# MCU_STM32.net
KiCad netlist of a schematic drawn in Altium Designer
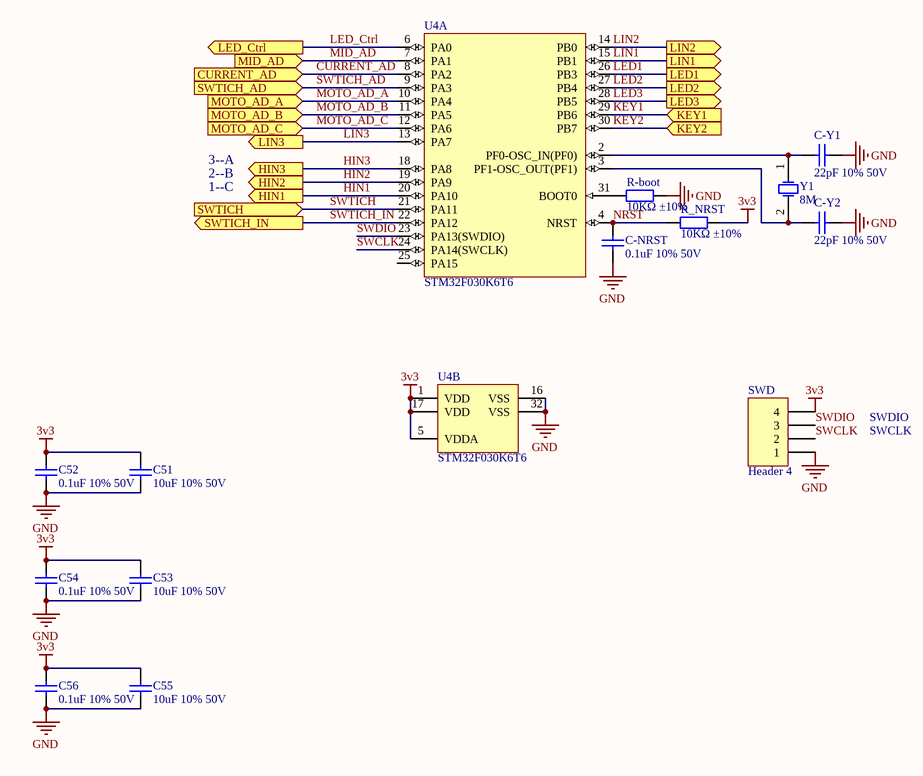
[diagram p0: MCU_STM32.SchDoc]

(export (version "E")
  (design (tool "Eeschema 10.0.6"))
  (components
    (comp (ref "C-NRST")
      (value "0.1uF 10% 50V")
      (footprint "0603_C")
      (description "贴片电容")
      (libsource (lib "Cap") (part "0603 4.7uF (475) 10% 16V"))
    )
    (comp (ref "C-Y1")
      (value "22pF 10% 50V")
      (footprint "0603_C")
      (description "贴片电容")
      (libsource (lib "Cap") (part "0603 4.7uF (475) 10% 16V"))
    )
    (comp (ref "C-Y2")
      (value "22pF 10% 50V")
      (footprint "0603_C")
      (description "贴片电容")
      (libsource (lib "Cap") (part "0603 4.7uF (475) 10% 16V"))
    )
    (comp (ref "C51")
      (value "10uF 10% 50V")
      (footprint "0805_C")
      (description "贴片电容")
      (libsource (lib "Cap") (part "0805 1uF (105) 10% 50V"))
    )
    (comp (ref "C52")
      (value "0.1uF 10% 50V")
      (footprint "0603_C")
      (description "贴片电容")
      (libsource (lib "Cap") (part "0603 4.7uF (475) 10% 16V"))
    )
    (comp (ref "C53")
      (value "10uF 10% 50V")
      (footprint "0805_C")
      (description "贴片电容")
      (libsource (lib "Cap") (part "0805 1uF (105) 10% 50V"))
    )
    (comp (ref "C54")
      (value "0.1uF 10% 50V")
      (footprint "0603_C")
      (description "贴片电容")
      (libsource (lib "Cap") (part "0603 4.7uF (475) 10% 16V"))
    )
    (comp (ref "C55")
      (value "10uF 10% 50V")
      (footprint "0805_C")
      (description "贴片电容")
      (libsource (lib "Cap") (part "0805 1uF (105) 10% 50V"))
    )
    (comp (ref "C56")
      (value "0.1uF 10% 50V")
      (footprint "0603_C")
      (description "贴片电容")
      (libsource (lib "Cap") (part "0603 4.7uF (475) 10% 16V"))
    )
    (comp (ref "R-boot")
      (value "10KΩ ±10%")
      (footprint "0603_R")
      (description "贴片电阻")
      (libsource (lib "RES") (part "0603 2.2Ω (2R20) 1%"))
    )
    (comp (ref "R_NRST")
      (value "10KΩ ±10%")
      (footprint "0603_R")
      (description "贴片电阻")
      (libsource (lib "RES") (part "0603 2.2Ω (2R20) 1%"))
    )
    (comp (ref "SWD")
      (value "Header 4")
      (footprint "FPC_1.25_4P")
      (description "Header, 4-Pin")
      (fields (field (name "PUBLISHER") "Altium Limited"))
      (libsource (lib "Miscellaneous Connectors") (part "Header 4"))
    )
    (comp (ref "U4")
      (value "STM32F030K6T6")
      (footprint "STM-LQFP32_M")
      (libsource (lib "MySTM32F0") (part "MC-ARM-STM32F030-SQ32"))
    )
    (comp (ref "Y1")
      (value "8M")
      (footprint "XTAL")
      (description "Crystal Oscillator")
      (fields (field (name "PUBLISHER") "Altium Limited"))
      (libsource (lib "Miscellaneous Devices") (part "XTAL"))
    )
  )
  (nets
    (net (code "1") (name "/CURRENT_AD") (class "Default")
      (node (ref "U4") (pin "8") (pinfunction "PA2_8") (pintype "bidirectional"))
    )
    (net (code "2") (name "/HIN1") (class "Default")
      (node (ref "U4") (pin "20") (pinfunction "PA10_20") (pintype "bidirectional"))
    )
    (net (code "3") (name "/HIN2") (class "Default")
      (node (ref "U4") (pin "19") (pinfunction "PA9_19") (pintype "bidirectional"))
    )
    (net (code "4") (name "/HIN3") (class "Default")
      (node (ref "U4") (pin "18") (pinfunction "PA8_18") (pintype "bidirectional"))
    )
    (net (code "5") (name "/KEY1") (class "Default")
      (node (ref "U4") (pin "29") (pinfunction "PB6_29") (pintype "bidirectional"))
    )
    (net (code "6") (name "/KEY2") (class "Default")
      (node (ref "U4") (pin "30") (pinfunction "PB7_30") (pintype "bidirectional"))
    )
    (net (code "7") (name "/LED1") (class "Default")
      (node (ref "U4") (pin "26") (pinfunction "PB3_26") (pintype "bidirectional"))
    )
    (net (code "8") (name "/LED2") (class "Default")
      (node (ref "U4") (pin "27") (pinfunction "PB4_27") (pintype "bidirectional"))
    )
    (net (code "9") (name "/LED3") (class "Default")
      (node (ref "U4") (pin "28") (pinfunction "PB5_28") (pintype "bidirectional"))
    )
    (net (code "10") (name "/LED_Ctrl") (class "Default")
      (node (ref "U4") (pin "6") (pinfunction "PA0_6") (pintype "bidirectional"))
    )
    (net (code "11") (name "/LIN1") (class "Default")
      (node (ref "U4") (pin "15") (pinfunction "PB1_15") (pintype "bidirectional"))
    )
    (net (code "12") (name "/LIN2") (class "Default")
      (node (ref "U4") (pin "14") (pinfunction "PB0_14") (pintype "bidirectional"))
    )
    (net (code "13") (name "/LIN3") (class "Default")
      (node (ref "U4") (pin "13") (pinfunction "PA7_13") (pintype "bidirectional"))
    )
    (net (code "14") (name "/MID_AD") (class "Default")
      (node (ref "U4") (pin "7") (pinfunction "PA1_7") (pintype "bidirectional"))
    )
    (net (code "15") (name "/MOTO_AD_A") (class "Default")
      (node (ref "U4") (pin "10") (pinfunction "PA4_10") (pintype "bidirectional"))
    )
    (net (code "16") (name "/MOTO_AD_B") (class "Default")
      (node (ref "U4") (pin "11") (pinfunction "PA5_11") (pintype "bidirectional"))
    )
    (net (code "17") (name "/MOTO_AD_C") (class "Default")
      (node (ref "U4") (pin "12") (pinfunction "PA6_12") (pintype "bidirectional"))
    )
    (net (code "18") (name "/NRST") (class "Default")
      (node (ref "C-NRST") (pin "2") (pinfunction "2_2") (pintype "passive"))
      (node (ref "R_NRST") (pin "2") (pinfunction "2_2") (pintype "passive"))
      (node (ref "U4") (pin "4") (pinfunction "NRST_4") (pintype "bidirectional"))
    )
    (net (code "19") (name "/SWCLK") (class "Default")
      (node (ref "SWD") (pin "2") (pinfunction "2_2") (pintype "passive"))
      (node (ref "U4") (pin "24") (pinfunction "PA14(SWCLK)_24") (pintype "bidirectional"))
    )
    (net (code "20") (name "/SWDIO") (class "Default")
      (node (ref "SWD") (pin "3") (pinfunction "3_3") (pintype "passive"))
      (node (ref "U4") (pin "23") (pinfunction "PA13(SWDIO)_23") (pintype "bidirectional"))
    )
    (net (code "21") (name "/SWTICH") (class "Default")
      (node (ref "U4") (pin "21") (pinfunction "PA11_21") (pintype "bidirectional"))
    )
    (net (code "22") (name "/SWTICH_AD") (class "Default")
      (node (ref "U4") (pin "9") (pinfunction "PA3_9") (pintype "bidirectional"))
    )
    (net (code "23") (name "/SWTICH_IN") (class "Default")
      (node (ref "U4") (pin "22") (pinfunction "PA12_22") (pintype "bidirectional"))
    )
    (net (code "24") (name "3v3") (class "Default")
      (node (ref "C51") (pin "2") (pinfunction "2_2") (pintype "passive"))
      (node (ref "C52") (pin "2") (pinfunction "2_2") (pintype "passive"))
      (node (ref "C53") (pin "2") (pinfunction "2_2") (pintype "passive"))
      (node (ref "C54") (pin "2") (pinfunction "2_2") (pintype "passive"))
      (node (ref "C55") (pin "2") (pinfunction "2_2") (pintype "passive"))
      (node (ref "C56") (pin "2") (pinfunction "2_2") (pintype "passive"))
      (node (ref "R_NRST") (pin "1") (pinfunction "1_1") (pintype "passive"))
      (node (ref "SWD") (pin "4") (pinfunction "4_4") (pintype "passive"))
      (node (ref "U4") (pin "1") (pinfunction "VDD_1") (pintype "power_in"))
      (node (ref "U4") (pin "17") (pinfunction "VDD_17") (pintype "power_in"))
      (node (ref "U4") (pin "5") (pinfunction "VDDA_5") (pintype "power_in"))
    )
    (net (code "25") (name "GND") (class "Default")
      (node (ref "C-NRST") (pin "1") (pinfunction "1_1") (pintype "passive"))
      (node (ref "C-Y1") (pin "1") (pinfunction "1_1") (pintype "passive"))
      (node (ref "C-Y2") (pin "1") (pinfunction "1_1") (pintype "passive"))
      (node (ref "C51") (pin "1") (pinfunction "1_1") (pintype "passive"))
      (node (ref "C52") (pin "1") (pinfunction "1_1") (pintype "passive"))
      (node (ref "C53") (pin "1") (pinfunction "1_1") (pintype "passive"))
      (node (ref "C54") (pin "1") (pinfunction "1_1") (pintype "passive"))
      (node (ref "C55") (pin "1") (pinfunction "1_1") (pintype "passive"))
      (node (ref "C56") (pin "1") (pinfunction "1_1") (pintype "passive"))
      (node (ref "R-boot") (pin "1") (pinfunction "1_1") (pintype "passive"))
      (node (ref "SWD") (pin "1") (pinfunction "1_1") (pintype "passive"))
      (node (ref "U4") (pin "16") (pinfunction "VSS_16") (pintype "power_in"))
      (node (ref "U4") (pin "32") (pinfunction "VSS_32") (pintype "power_in"))
    )
    (net (code "26") (name "Net-(U4A-BOOT0)") (class "Default")
      (node (ref "R-boot") (pin "2") (pinfunction "2_2") (pintype "passive"))
      (node (ref "U4") (pin "31") (pinfunction "BOOT0_31") (pintype "input"))
    )
    (net (code "27") (name "Net-(U4A-PF0-OSC_IN(PF0))") (class "Default")
      (node (ref "C-Y1") (pin "2") (pinfunction "2_2") (pintype "passive"))
      (node (ref "U4") (pin "2") (pinfunction "PF0-OSC_IN(PF0)_2") (pintype "bidirectional"))
      (node (ref "Y1") (pin "1") (pinfunction "OSC1_1") (pintype "passive"))
    )
    (net (code "28") (name "Net-(U4A-PF1-OSC_OUT(PF1))") (class "Default")
      (node (ref "C-Y2") (pin "2") (pinfunction "2_2") (pintype "passive"))
      (node (ref "U4") (pin "3") (pinfunction "PF1-OSC_OUT(PF1)_3") (pintype "bidirectional"))
      (node (ref "Y1") (pin "2") (pinfunction "OSC2_2") (pintype "passive"))
    )
    (net (code "29") (name "unconnected-(U4A-PA15-Pad25)") (class "Default")
      (node (ref "U4") (pin "25") (pinfunction "PA15_25") (pintype "bidirectional"))
    )
  )
)
